# ARTSi-v5.net
KiCad netlist of a schematic drawn in EAGLE
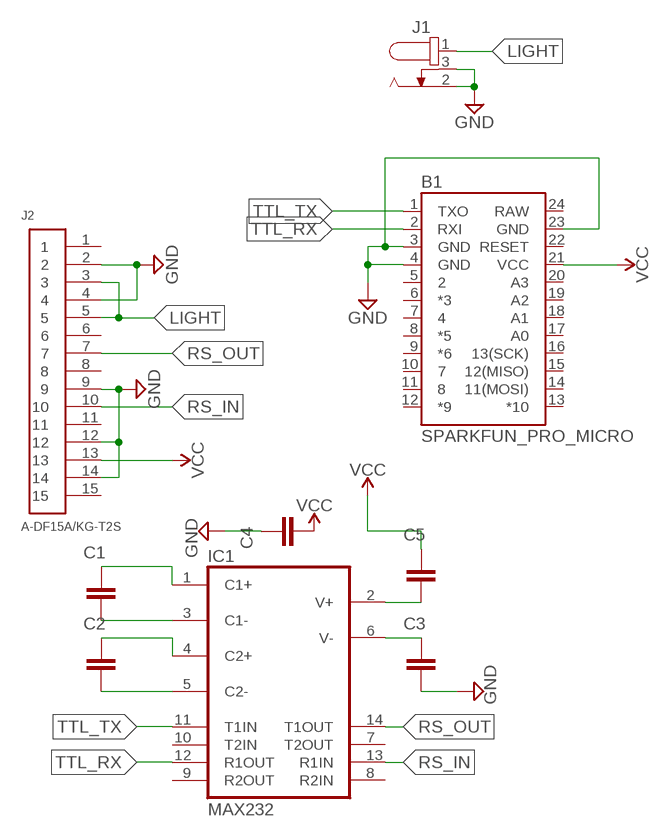
[diagram p0: schematic, sheet 1]

(export (version "E")
  (design (tool "Eeschema 10.0.6"))
  (components
    (comp (ref "B1")
      (value "SPARKFUN_PRO_MICRO")
      (footprint "eagle-import:SPARKFUN_PRO_MICRO")
      (libsource (lib "eagle-import") (part "SPARKFUN_PRO_MICRO"))
    )
    (comp (ref "C1")
      (value "CC0805KRX7R9BB104")
      (footprint "eagle-import:CAP_0805")
      (fields
        (field (name "DIGIKEY_PART_NUMBER") "311-1140-2-ND")
        (field (name "MANUFACTURER") "Yageo")
        (field (name "CREATED_BY") "PCBLayout.com")
      )
      (libsource (lib "eagle-import") (part "CC0805KRX7R9BB104"))
    )
    (comp (ref "C2")
      (value "CC0805KRX7R9BB104")
      (footprint "eagle-import:CAP_0805")
      (fields
        (field (name "DIGIKEY_PART_NUMBER") "311-1140-2-ND")
        (field (name "MANUFACTURER") "Yageo")
        (field (name "CREATED_BY") "PCBLayout.com")
      )
      (libsource (lib "eagle-import") (part "CC0805KRX7R9BB104"))
    )
    (comp (ref "C3")
      (value "CC0805KRX7R9BB104")
      (footprint "eagle-import:CAP_0805")
      (fields
        (field (name "DIGIKEY_PART_NUMBER") "311-1140-2-ND")
        (field (name "MANUFACTURER") "Yageo")
        (field (name "CREATED_BY") "PCBLayout.com")
      )
      (libsource (lib "eagle-import") (part "CC0805KRX7R9BB104"))
    )
    (comp (ref "C4")
      (value "CC0805KRX7R9BB104")
      (footprint "eagle-import:CAP_0805")
      (fields
        (field (name "DIGIKEY_PART_NUMBER") "311-1140-2-ND")
        (field (name "MANUFACTURER") "Yageo")
        (field (name "CREATED_BY") "PCBLayout.com")
      )
      (libsource (lib "eagle-import") (part "CC0805KRX7R9BB104"))
    )
    (comp (ref "C5")
      (value "CC0805KRX7R9BB104")
      (footprint "eagle-import:CAP_0805")
      (fields
        (field (name "DIGIKEY_PART_NUMBER") "311-1140-2-ND")
        (field (name "MANUFACTURER") "Yageo")
        (field (name "CREATED_BY") "PCBLayout.com")
      )
      (libsource (lib "eagle-import") (part "CC0805KRX7R9BB104"))
    )
    (comp (ref "IC1")
      (value "MAX232")
      (footprint "eagle-import:DIL16")
      (fields (field (name "MF") "MAXIM") (field (name "MPN") "MAX232ACPE+"))
      (libsource (lib "eagle-import") (part "MAX232"))
    )
    (comp (ref "J1")
      (value "694108301002")
      (footprint "eagle-import:694108301002")
      (libsource (lib "eagle-import") (part "694108301002"))
    )
    (comp (ref "J2")
      (value "A-DF15A/KG-T2S")
      (footprint "eagle-import:A-DF15A_KG-T2S")
      (fields
        (field (name "DIGI_KEY_PART_NUMBER") "AE10929-ND")
        (field (name "MANUFACTURER") "Assmann WSW Components")
        (field (name "MPN") "A-DF 15 A/KG-T2S")
        (field (name "CREATED_BY") "PCBLayout.com")
      )
      (libsource (lib "eagle-import") (part "A-DF15A/KG-T2S"))
    )
  )
  (nets
    (net (code "1") (name "/RAW") (class "Default")
      (node (ref "B1") (pin "24") (pinfunction "RAW_24") (pintype "power_in"))
    )
    (net (code "2") (name "GND") (class "Default")
      (node (ref "B1") (pin "23") (pinfunction "GND_23") (pintype "power_in"))
      (node (ref "B1") (pin "3") (pinfunction "GND_3") (pintype "power_in"))
      (node (ref "B1") (pin "4") (pinfunction "GND_4") (pintype "power_in"))
      (node (ref "C3") (pin "2") (pinfunction "2_2") (pintype "passive"))
      (node (ref "C4") (pin "1") (pinfunction "1_1") (pintype "passive"))
      (node (ref "J1") (pin "2") (pinfunction "2_2") (pintype "passive"))
      (node (ref "J1") (pin "3") (pinfunction "3_3") (pintype "passive"))
      (node (ref "J2") (pin "12") (pinfunction "12_12") (pintype "passive"))
      (node (ref "J2") (pin "14") (pinfunction "14_14") (pintype "passive"))
      (node (ref "J2") (pin "2") (pinfunction "2_2") (pintype "passive"))
      (node (ref "J2") (pin "4") (pinfunction "4_4") (pintype "passive"))
      (node (ref "J2") (pin "9") (pinfunction "9_9") (pintype "passive"))
    )
    (net (code "3") (name "LIGHT") (class "Default")
      (node (ref "J1") (pin "1") (pinfunction "1_1") (pintype "passive"))
      (node (ref "J2") (pin "3") (pinfunction "3_3") (pintype "passive"))
      (node (ref "J2") (pin "5") (pinfunction "5_5") (pintype "passive"))
    )
    (net (code "4") (name "Net-(IC1A-C1+)") (class "Default")
      (node (ref "C1") (pin "1") (pinfunction "1_1") (pintype "passive"))
      (node (ref "IC1") (pin "1") (pinfunction "C1+_1") (pintype "bidirectional"))
    )
    (net (code "5") (name "Net-(IC1A-C1-)") (class "Default")
      (node (ref "C1") (pin "2") (pinfunction "2_2") (pintype "passive"))
      (node (ref "IC1") (pin "3") (pinfunction "C1-_3") (pintype "bidirectional"))
    )
    (net (code "6") (name "Net-(IC1A-C2+)") (class "Default")
      (node (ref "C2") (pin "1") (pinfunction "1_1") (pintype "passive"))
      (node (ref "IC1") (pin "4") (pinfunction "C2+_4") (pintype "bidirectional"))
    )
    (net (code "7") (name "Net-(IC1A-C2-)") (class "Default")
      (node (ref "C2") (pin "2") (pinfunction "2_2") (pintype "passive"))
      (node (ref "IC1") (pin "5") (pinfunction "C2-_5") (pintype "bidirectional"))
    )
    (net (code "8") (name "Net-(IC1A-V+)") (class "Default")
      (node (ref "C5") (pin "2") (pinfunction "2_2") (pintype "passive"))
      (node (ref "IC1") (pin "2") (pinfunction "V+_2") (pintype "bidirectional"))
    )
    (net (code "9") (name "Net-(IC1A-V-)") (class "Default")
      (node (ref "C3") (pin "1") (pinfunction "1_1") (pintype "passive"))
      (node (ref "IC1") (pin "6") (pinfunction "V-_6") (pintype "bidirectional"))
    )
    (net (code "10") (name "RS_IN") (class "Default")
      (node (ref "IC1") (pin "13") (pinfunction "R1IN_13") (pintype "input"))
      (node (ref "J2") (pin "10") (pinfunction "10_10") (pintype "passive"))
    )
    (net (code "11") (name "RS_OUT") (class "Default")
      (node (ref "IC1") (pin "14") (pinfunction "T1OUT_14") (pintype "output"))
      (node (ref "J2") (pin "7") (pinfunction "7_7") (pintype "passive"))
    )
    (net (code "12") (name "TTL_RX") (class "Default")
      (node (ref "B1") (pin "2") (pinfunction "RXI_2") (pintype "bidirectional"))
      (node (ref "IC1") (pin "12") (pinfunction "R1OUT_12") (pintype "output"))
    )
    (net (code "13") (name "TTL_TX") (class "Default")
      (node (ref "B1") (pin "1") (pinfunction "TXO_1") (pintype "bidirectional"))
      (node (ref "IC1") (pin "11") (pinfunction "T1IN_11") (pintype "input"))
    )
    (net (code "14") (name "VCC") (class "Default")
      (node (ref "B1") (pin "21") (pinfunction "VCC_21") (pintype "power_in"))
      (node (ref "C4") (pin "2") (pinfunction "2_2") (pintype "passive"))
      (node (ref "C5") (pin "1") (pinfunction "1_1") (pintype "passive"))
      (node (ref "J2") (pin "13") (pinfunction "13_13") (pintype "passive"))
    )
    (net (code "15") (name "unconnected-(B1-*3-Pad6)") (class "Default")
      (node (ref "B1") (pin "6") (pinfunction "*3_6") (pintype "bidirectional"))
    )
    (net (code "16") (name "unconnected-(B1-*5-Pad8)") (class "Default")
      (node (ref "B1") (pin "8") (pinfunction "*5_8") (pintype "bidirectional"))
    )
    (net (code "17") (name "unconnected-(B1-*6-Pad9)") (class "Default")
      (node (ref "B1") (pin "9") (pinfunction "*6_9") (pintype "bidirectional"))
    )
    (net (code "18") (name "unconnected-(B1-*9-Pad12)") (class "Default")
      (node (ref "B1") (pin "12") (pinfunction "*9_12") (pintype "bidirectional"))
    )
    (net (code "19") (name "unconnected-(B1-*10-Pad13)") (class "Default")
      (node (ref "B1") (pin "13") (pinfunction "*10_13") (pintype "bidirectional"))
    )
    (net (code "20") (name "unconnected-(B1-2-Pad5)") (class "Default")
      (node (ref "B1") (pin "5") (pinfunction "2_5") (pintype "bidirectional"))
    )
    (net (code "21") (name "unconnected-(B1-4-Pad7)") (class "Default")
      (node (ref "B1") (pin "7") (pinfunction "4_7") (pintype "bidirectional"))
    )
    (net (code "22") (name "unconnected-(B1-7-Pad10)") (class "Default")
      (node (ref "B1") (pin "10") (pinfunction "7_10") (pintype "bidirectional"))
    )
    (net (code "23") (name "unconnected-(B1-8-Pad11)") (class "Default")
      (node (ref "B1") (pin "11") (pinfunction "8_11") (pintype "bidirectional"))
    )
    (net (code "24") (name "unconnected-(B1-11(MOSI)-Pad14)") (class "Default")
      (node (ref "B1") (pin "14") (pinfunction "11(MOSI)_14") (pintype "bidirectional"))
    )
    (net (code "25") (name "unconnected-(B1-12(MISO)-Pad15)") (class "Default")
      (node (ref "B1") (pin "15") (pinfunction "12(MISO)_15") (pintype "bidirectional"))
    )
    (net (code "26") (name "unconnected-(B1-13(SCK)-Pad16)") (class "Default")
      (node (ref "B1") (pin "16") (pinfunction "13(SCK)_16") (pintype "bidirectional"))
    )
    (net (code "27") (name "unconnected-(B1-A0-Pad17)") (class "Default")
      (node (ref "B1") (pin "17") (pinfunction "A0_17") (pintype "bidirectional"))
    )
    (net (code "28") (name "unconnected-(B1-A1-Pad18)") (class "Default")
      (node (ref "B1") (pin "18") (pinfunction "A1_18") (pintype "bidirectional"))
    )
    (net (code "29") (name "unconnected-(B1-A2-Pad19)") (class "Default")
      (node (ref "B1") (pin "19") (pinfunction "A2_19") (pintype "bidirectional"))
    )
    (net (code "30") (name "unconnected-(B1-A3-Pad20)") (class "Default")
      (node (ref "B1") (pin "20") (pinfunction "A3_20") (pintype "bidirectional"))
    )
    (net (code "31") (name "unconnected-(B1-RESET-Pad22)") (class "Default")
      (node (ref "B1") (pin "22") (pinfunction "RESET_22") (pintype "bidirectional"))
    )
    (net (code "32") (name "unconnected-(IC1A-R2IN-Pad8)") (class "Default")
      (node (ref "IC1") (pin "8") (pinfunction "R2IN_8") (pintype "input"))
    )
    (net (code "33") (name "unconnected-(IC1A-R2OUT-Pad9)") (class "Default")
      (node (ref "IC1") (pin "9") (pinfunction "R2OUT_9") (pintype "output"))
    )
    (net (code "34") (name "unconnected-(IC1A-T2IN-Pad10)") (class "Default")
      (node (ref "IC1") (pin "10") (pinfunction "T2IN_10") (pintype "input"))
    )
    (net (code "35") (name "unconnected-(IC1A-T2OUT-Pad7)") (class "Default")
      (node (ref "IC1") (pin "7") (pinfunction "T2OUT_7") (pintype "output"))
    )
    (net (code "36") (name "unconnected-(J2-Pad1)") (class "Default")
      (node (ref "J2") (pin "1") (pinfunction "1_1") (pintype "passive"))
    )
    (net (code "37") (name "unconnected-(J2-Pad6)") (class "Default")
      (node (ref "J2") (pin "6") (pinfunction "6_6") (pintype "passive"))
    )
    (net (code "38") (name "unconnected-(J2-Pad8)") (class "Default")
      (node (ref "J2") (pin "8") (pinfunction "8_8") (pintype "passive"))
    )
    (net (code "39") (name "unconnected-(J2-Pad11)") (class "Default")
      (node (ref "J2") (pin "11") (pinfunction "11_11") (pintype "passive"))
    )
    (net (code "40") (name "unconnected-(J2-Pad15)") (class "Default")
      (node (ref "J2") (pin "15") (pinfunction "15_15") (pintype "passive"))
    )
  )
)
